# power.net
KiCad netlist of a schematic drawn in Altium Designer
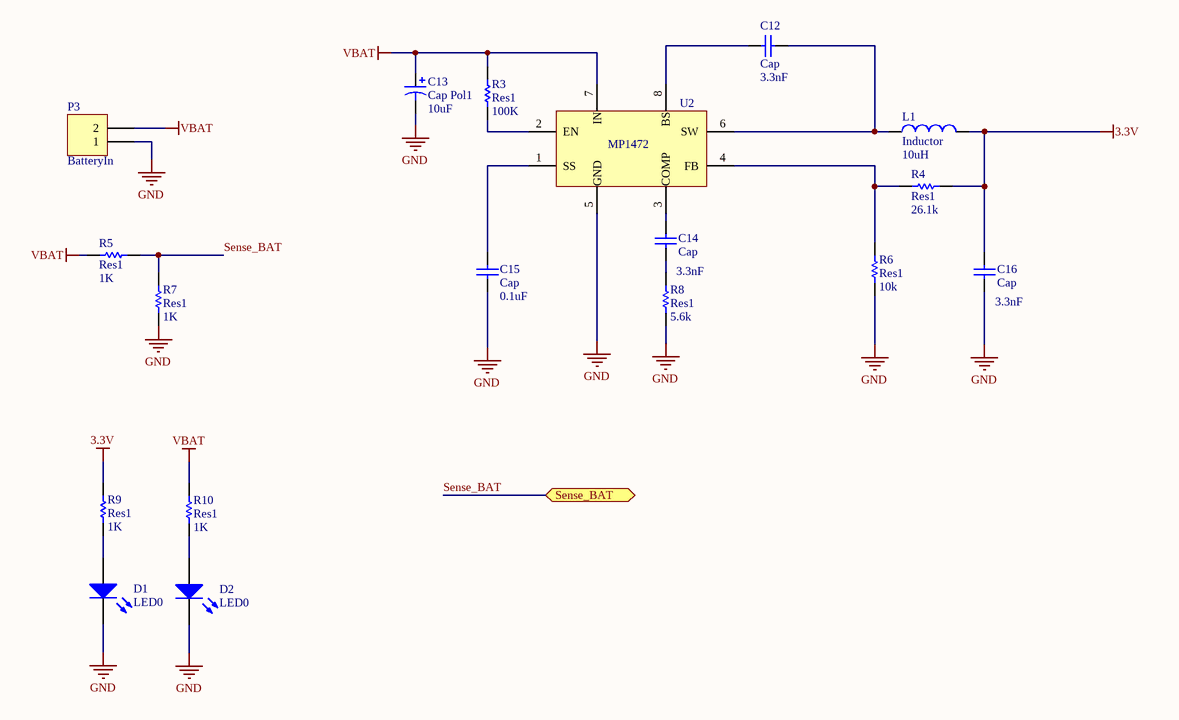
[diagram p0: power.SchDoc]

(export (version "E")
  (design (tool "Eeschema 10.0.6"))
  (components
    (comp (ref "C12")
      (value "Cap")
      (footprint "0805-CAP")
      (description "Capacitor")
      (fields (field (name "ALTIUM_VALUE") "3.3nF") (field (name "PUBLISHER") "Altium Limited"))
      (libsource (lib "Miscellaneous Devices") (part "Cap"))
    )
    (comp (ref "C13")
      (value "Cap Pol1")
      (footprint "Tantalum A-Case")
      (description "Polarized Capacitor (Radial)")
      (fields (field (name "ALTIUM_VALUE") "10uF") (field (name "PUBLISHER") "Altium Limited"))
      (libsource (lib "Miscellaneous Devices") (part "Cap Pol1"))
    )
    (comp (ref "C14")
      (value "Cap")
      (footprint "0805-CAP")
      (description "Capacitor")
      (fields (field (name "ALTIUM_VALUE") "3.3nF") (field (name "PUBLISHER") "Altium Limited"))
      (libsource (lib "Miscellaneous Devices") (part "Cap"))
    )
    (comp (ref "C15")
      (value "Cap")
      (footprint "0805-CAP")
      (description "Capacitor")
      (fields (field (name "ALTIUM_VALUE") "0.1uF") (field (name "PUBLISHER") "Altium Limited"))
      (libsource (lib "Miscellaneous Devices") (part "Cap"))
    )
    (comp (ref "C16")
      (value "Cap")
      (footprint "0805-CAP")
      (description "Capacitor")
      (fields (field (name "ALTIUM_VALUE") "3.3nF") (field (name "PUBLISHER") "Altium Limited"))
      (libsource (lib "Miscellaneous Devices") (part "Cap"))
    )
    (comp (ref "D1")
      (value "LED0")
      (footprint "1206-LED RED")
      (description "Typical INFRARED GaAs LED")
      (fields (field (name "PUBLISHER") "Altium Limited"))
      (libsource (lib "Miscellaneous Devices") (part "LED0"))
    )
    (comp (ref "D2")
      (value "LED0")
      (footprint "1206-LED RED")
      (description "Typical INFRARED GaAs LED")
      (fields (field (name "PUBLISHER") "Altium Limited"))
      (libsource (lib "Miscellaneous Devices") (part "LED0"))
    )
    (comp (ref "L1")
      (value "Inductor")
      (footprint "DR125")
      (fields (field (name "ALTIUM_VALUE") "10uH") (field (name "PUBLISHER") "Altium Limited"))
      (libsource (lib "Miscellaneous Devices") (part "Inductor"))
    )
    (comp (ref "P3")
      (value "BatteryIn")
      (footprint "Battery 1")
      (description "Header, 2-Pin")
      (fields (field (name "PUBLISHER") "Altium Limited"))
      (libsource (lib "Miscellaneous Connectors") (part "Header 2"))
    )
    (comp (ref "R3")
      (value "Res1")
      (footprint "0805-RES")
      (description "Resistor")
      (fields (field (name "ALTIUM_VALUE") "100K") (field (name "PUBLISHER") "Altium Limited"))
      (libsource (lib "Miscellaneous Devices") (part "Res1"))
    )
    (comp (ref "R4")
      (value "Res1")
      (footprint "0805-RES")
      (description "Resistor")
      (fields (field (name "ALTIUM_VALUE") "26.1k") (field (name "PUBLISHER") "Altium Limited"))
      (libsource (lib "Miscellaneous Devices") (part "Res1"))
    )
    (comp (ref "R5")
      (value "Res1")
      (footprint "0805-RES")
      (description "Resistor")
      (fields (field (name "ALTIUM_VALUE") "1K") (field (name "PUBLISHER") "Altium Limited"))
      (libsource (lib "Miscellaneous Devices") (part "Res1"))
    )
    (comp (ref "R6")
      (value "Res1")
      (footprint "0805-RES")
      (description "Resistor")
      (fields (field (name "ALTIUM_VALUE") "10k") (field (name "PUBLISHER") "Altium Limited"))
      (libsource (lib "Miscellaneous Devices") (part "Res1"))
    )
    (comp (ref "R7")
      (value "Res1")
      (footprint "0805-RES")
      (description "Resistor")
      (fields (field (name "ALTIUM_VALUE") "1K") (field (name "PUBLISHER") "Altium Limited"))
      (libsource (lib "Miscellaneous Devices") (part "Res1"))
    )
    (comp (ref "R8")
      (value "Res1")
      (footprint "0805-RES")
      (description "Resistor")
      (fields (field (name "ALTIUM_VALUE") "5.6k") (field (name "PUBLISHER") "Altium Limited"))
      (libsource (lib "Miscellaneous Devices") (part "Res1"))
    )
    (comp (ref "R9")
      (value "Res1")
      (footprint "0805-RES")
      (description "Resistor")
      (fields (field (name "ALTIUM_VALUE") "1K") (field (name "PUBLISHER") "Altium Limited"))
      (libsource (lib "Miscellaneous Devices") (part "Res1"))
    )
    (comp (ref "R10")
      (value "Res1")
      (footprint "0805-RES")
      (description "Resistor")
      (fields (field (name "ALTIUM_VALUE") "1K") (field (name "PUBLISHER") "Altium Limited"))
      (libsource (lib "Miscellaneous Devices") (part "Res1"))
    )
    (comp (ref "U2")
      (value "MP1472")
      (footprint "TSOP-23")
      (description "MP1472 2A 18V Step-Down Conventor")
      (libsource (lib "IC-Schematics") (part "MP1472"))
    )
  )
  (nets
    (net (code "1") (name "/Sense_BAT") (class "Default")
      (node (ref "R5") (pin "2") (pinfunction "2_2") (pintype "passive"))
      (node (ref "R7") (pin "1") (pinfunction "1_1") (pintype "passive"))
    )
    (net (code "2") (name "3.3V") (class "Default")
      (node (ref "C16") (pin "1") (pinfunction "1_1") (pintype "passive"))
      (node (ref "L1") (pin "2") (pinfunction "2_2") (pintype "passive"))
      (node (ref "R4") (pin "2") (pinfunction "2_2") (pintype "passive"))
      (node (ref "R9") (pin "2") (pinfunction "2_2") (pintype "passive"))
    )
    (net (code "3") (name "GND") (class "Default")
      (node (ref "C13") (pin "2") (pinfunction "2_2") (pintype "passive"))
      (node (ref "C15") (pin "2") (pinfunction "2_2") (pintype "passive"))
      (node (ref "C16") (pin "2") (pinfunction "2_2") (pintype "passive"))
      (node (ref "D1") (pin "2") (pinfunction "K_2") (pintype "passive"))
      (node (ref "D2") (pin "2") (pinfunction "K_2") (pintype "passive"))
      (node (ref "P3") (pin "1") (pinfunction "1_1") (pintype "passive"))
      (node (ref "R6") (pin "1") (pinfunction "1_1") (pintype "passive"))
      (node (ref "R7") (pin "2") (pinfunction "2_2") (pintype "passive"))
      (node (ref "R8") (pin "2") (pinfunction "2_2") (pintype "passive"))
      (node (ref "U2") (pin "5") (pinfunction "GND_5") (pintype "passive"))
    )
    (net (code "4") (name "Net-(C14-Pad2)") (class "Default")
      (node (ref "C14") (pin "2") (pinfunction "2_2") (pintype "passive"))
      (node (ref "R8") (pin "1") (pinfunction "1_1") (pintype "passive"))
    )
    (net (code "5") (name "Net-(D1-A)") (class "Default")
      (node (ref "D1") (pin "1") (pinfunction "A_1") (pintype "passive"))
      (node (ref "R9") (pin "1") (pinfunction "1_1") (pintype "passive"))
    )
    (net (code "6") (name "Net-(D2-A)") (class "Default")
      (node (ref "D2") (pin "1") (pinfunction "A_1") (pintype "passive"))
      (node (ref "R10") (pin "1") (pinfunction "1_1") (pintype "passive"))
    )
    (net (code "7") (name "Net-(U2-BS)") (class "Default")
      (node (ref "C12") (pin "1") (pinfunction "1_1") (pintype "passive"))
      (node (ref "U2") (pin "8") (pinfunction "BS_8") (pintype "passive"))
    )
    (net (code "8") (name "Net-(U2-COMP)") (class "Default")
      (node (ref "C14") (pin "1") (pinfunction "1_1") (pintype "passive"))
      (node (ref "U2") (pin "3") (pinfunction "COMP_3") (pintype "passive"))
    )
    (net (code "9") (name "Net-(U2-EN)") (class "Default")
      (node (ref "R3") (pin "2") (pinfunction "2_2") (pintype "passive"))
      (node (ref "U2") (pin "2") (pinfunction "EN_2") (pintype "passive"))
    )
    (net (code "10") (name "Net-(U2-FB)") (class "Default")
      (node (ref "R4") (pin "1") (pinfunction "1_1") (pintype "passive"))
      (node (ref "R6") (pin "2") (pinfunction "2_2") (pintype "passive"))
      (node (ref "U2") (pin "4") (pinfunction "FB_4") (pintype "passive"))
    )
    (net (code "11") (name "Net-(U2-SS)") (class "Default")
      (node (ref "C15") (pin "1") (pinfunction "1_1") (pintype "passive"))
      (node (ref "U2") (pin "1") (pinfunction "SS_1") (pintype "passive"))
    )
    (net (code "12") (name "Net-(U2-SW)") (class "Default")
      (node (ref "C12") (pin "2") (pinfunction "2_2") (pintype "passive"))
      (node (ref "L1") (pin "1") (pinfunction "1_1") (pintype "passive"))
      (node (ref "U2") (pin "6") (pinfunction "SW_6") (pintype "passive"))
    )
    (net (code "13") (name "VBAT") (class "Default")
      (node (ref "C13") (pin "1") (pinfunction "1_1") (pintype "passive"))
      (node (ref "P3") (pin "2") (pinfunction "2_2") (pintype "passive"))
      (node (ref "R10") (pin "2") (pinfunction "2_2") (pintype "passive"))
      (node (ref "R3") (pin "1") (pinfunction "1_1") (pintype "passive"))
      (node (ref "R5") (pin "1") (pinfunction "1_1") (pintype "passive"))
      (node (ref "U2") (pin "7") (pinfunction "IN_7") (pintype "passive"))
    )
  )
)
